# Base_board_V1.net
KiCad netlist of a schematic drawn in EAGLE
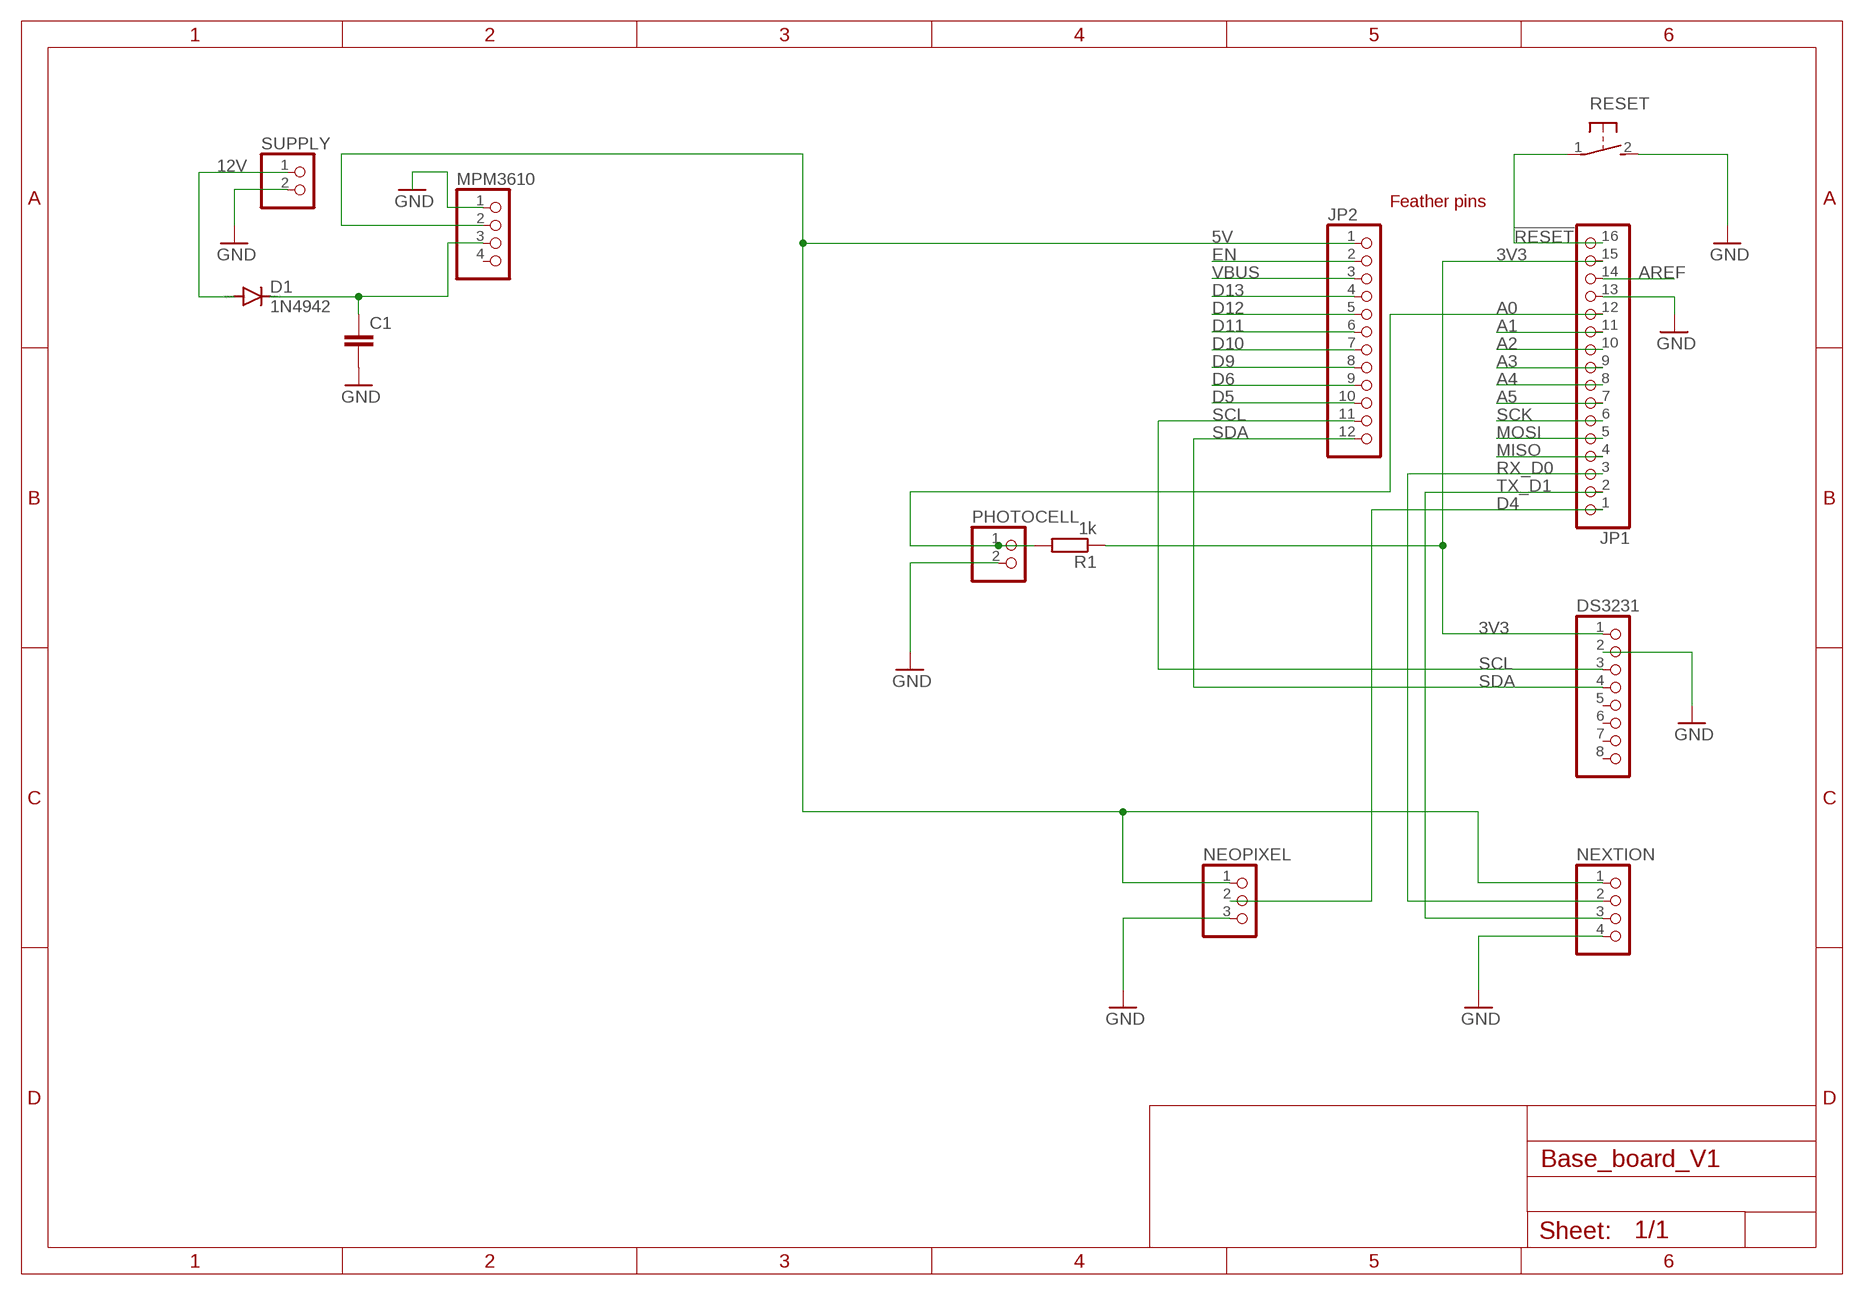
[diagram p0: schematic, sheet 1]

(export (version "E")
  (design (tool "Eeschema 10.0.6"))
  (components
    (comp (ref "C1")
      (value "C2,5-3")
      (footprint "eagle-import:C2.5-3")
      (libsource (lib "eagle-import") (part "C2,5-3"))
    )
    (comp (ref "D1")
      (value "1N4942")
      (footprint "eagle-import:DO41-10")
      (libsource (lib "eagle-import") (part "1N4942"))
    )
    (comp (ref "DS3231")
      (value "HEADER-1X870MIL")
      (footprint "eagle-import:1X08_ROUND_70")
      (libsource (lib "eagle-import") (part "HEADER-1X870MIL"))
    )
    (comp (ref "JP1")
      (value "HEADER-1X16ROUND")
      (footprint "eagle-import:1X16_ROUND")
      (libsource (lib "eagle-import") (part "HEADER-1X16ROUND"))
    )
    (comp (ref "JP2")
      (value "HEADER-1X12")
      (footprint "eagle-import:1X12_ROUND")
      (libsource (lib "eagle-import") (part "HEADER-1X12"))
    )
    (comp (ref "MPM3610")
      (value "PINHD-1X4")
      (footprint "eagle-import:1X04")
      (libsource (lib "eagle-import") (part "PINHD-1X4"))
    )
    (comp (ref "NEOPIXEL")
      (value "PINHD-1X3/90")
      (footprint "eagle-import:1X03_90")
      (libsource (lib "eagle-import") (part "PINHD-1X3/90"))
    )
    (comp (ref "NEXTION")
      (value "PINHD-1X4")
      (footprint "eagle-import:1X04")
      (libsource (lib "eagle-import") (part "PINHD-1X4"))
    )
    (comp (ref "PHOTOCELL")
      (value "PINHD-1X2/90")
      (footprint "eagle-import:1X02_90")
      (libsource (lib "eagle-import") (part "PINHD-1X2/90"))
    )
    (comp (ref "R1")
      (value "1k")
      (footprint "eagle-import:0207_10")
      (libsource (lib "eagle-import") (part "R-EU_0207/10"))
    )
    (comp (ref "RESET")
      (value "31-XX")
      (footprint "eagle-import:B3F-31XX")
      (fields (field (name "MPN") "B3F-3100"))
      (libsource (lib "eagle-import") (part "31-XX"))
    )
    (comp (ref "SUPPLY")
      (value "PINHD-1X2")
      (footprint "eagle-import:1X02")
      (libsource (lib "eagle-import") (part "PINHD-1X2"))
    )
  )
  (nets
    (net (code "1") (name "/3V3") (class "Default")
      (node (ref "DS3231") (pin "1") (pinfunction "1_1") (pintype "passive"))
      (node (ref "JP1") (pin "15") (pinfunction "15_15") (pintype "passive"))
      (node (ref "R1") (pin "1") (pinfunction "1_1") (pintype "passive"))
    )
    (net (code "2") (name "/5V") (class "Default")
      (node (ref "JP2") (pin "1") (pinfunction "1_1") (pintype "passive"))
      (node (ref "MPM3610") (pin "2") (pinfunction "2_2") (pintype "passive"))
      (node (ref "NEOPIXEL") (pin "1") (pinfunction "1_1") (pintype "passive"))
      (node (ref "NEXTION") (pin "1") (pinfunction "1_1") (pintype "passive"))
    )
    (net (code "3") (name "/12V") (class "Default")
      (node (ref "D1") (pin "A") (pinfunction "A_A") (pintype "passive"))
      (node (ref "SUPPLY") (pin "1") (pinfunction "1_1") (pintype "passive"))
    )
    (net (code "4") (name "/A0") (class "Default")
      (node (ref "JP1") (pin "12") (pinfunction "12_12") (pintype "passive"))
      (node (ref "PHOTOCELL") (pin "1") (pinfunction "1_1") (pintype "passive"))
      (node (ref "R1") (pin "2") (pinfunction "2_2") (pintype "passive"))
    )
    (net (code "5") (name "/A1") (class "Default")
      (node (ref "JP1") (pin "11") (pinfunction "11_11") (pintype "passive"))
    )
    (net (code "6") (name "/A2") (class "Default")
      (node (ref "JP1") (pin "10") (pinfunction "10_10") (pintype "passive"))
    )
    (net (code "7") (name "/A3") (class "Default")
      (node (ref "JP1") (pin "9") (pinfunction "9_9") (pintype "passive"))
    )
    (net (code "8") (name "/A4") (class "Default")
      (node (ref "JP1") (pin "8") (pinfunction "8_8") (pintype "passive"))
    )
    (net (code "9") (name "/A5") (class "Default")
      (node (ref "JP1") (pin "7") (pinfunction "7_7") (pintype "passive"))
    )
    (net (code "10") (name "/AREF") (class "Default")
      (node (ref "JP1") (pin "14") (pinfunction "14_14") (pintype "passive"))
    )
    (net (code "11") (name "/D4") (class "Default")
      (node (ref "JP1") (pin "1") (pinfunction "1_1") (pintype "passive"))
      (node (ref "NEOPIXEL") (pin "2") (pinfunction "2_2") (pintype "passive"))
    )
    (net (code "12") (name "/D5") (class "Default")
      (node (ref "JP2") (pin "10") (pinfunction "10_10") (pintype "passive"))
    )
    (net (code "13") (name "/D6") (class "Default")
      (node (ref "JP2") (pin "9") (pinfunction "9_9") (pintype "passive"))
    )
    (net (code "14") (name "/D9") (class "Default")
      (node (ref "JP2") (pin "8") (pinfunction "8_8") (pintype "passive"))
    )
    (net (code "15") (name "/D10") (class "Default")
      (node (ref "JP2") (pin "7") (pinfunction "7_7") (pintype "passive"))
    )
    (net (code "16") (name "/D11") (class "Default")
      (node (ref "JP2") (pin "6") (pinfunction "6_6") (pintype "passive"))
    )
    (net (code "17") (name "/D12") (class "Default")
      (node (ref "JP2") (pin "5") (pinfunction "5_5") (pintype "passive"))
    )
    (net (code "18") (name "/D13") (class "Default")
      (node (ref "JP2") (pin "4") (pinfunction "4_4") (pintype "passive"))
    )
    (net (code "19") (name "/EN") (class "Default")
      (node (ref "JP2") (pin "2") (pinfunction "2_2") (pintype "passive"))
    )
    (net (code "20") (name "/MISO") (class "Default")
      (node (ref "JP1") (pin "4") (pinfunction "4_4") (pintype "passive"))
    )
    (net (code "21") (name "/MOSI") (class "Default")
      (node (ref "JP1") (pin "5") (pinfunction "5_5") (pintype "passive"))
    )
    (net (code "22") (name "/RX_D0") (class "Default")
      (node (ref "JP1") (pin "3") (pinfunction "3_3") (pintype "passive"))
      (node (ref "NEXTION") (pin "2") (pinfunction "2_2") (pintype "passive"))
    )
    (net (code "23") (name "/SCK") (class "Default")
      (node (ref "JP1") (pin "6") (pinfunction "6_6") (pintype "passive"))
    )
    (net (code "24") (name "/SCL") (class "Default")
      (node (ref "DS3231") (pin "3") (pinfunction "3_3") (pintype "passive"))
      (node (ref "JP2") (pin "11") (pinfunction "11_11") (pintype "passive"))
    )
    (net (code "25") (name "/SDA") (class "Default")
      (node (ref "DS3231") (pin "4") (pinfunction "4_4") (pintype "passive"))
      (node (ref "JP2") (pin "12") (pinfunction "12_12") (pintype "passive"))
    )
    (net (code "26") (name "/TX_D1") (class "Default")
      (node (ref "JP1") (pin "2") (pinfunction "2_2") (pintype "passive"))
      (node (ref "NEXTION") (pin "3") (pinfunction "3_3") (pintype "passive"))
    )
    (net (code "27") (name "/VBUS") (class "Default")
      (node (ref "JP2") (pin "3") (pinfunction "3_3") (pintype "passive"))
    )
    (net (code "28") (name "/~{RESET}") (class "Default")
      (node (ref "JP1") (pin "16") (pinfunction "16_16") (pintype "passive"))
      (node (ref "RESET") (pin "1") (pinfunction "P_1") (pintype "passive"))
    )
    (net (code "29") (name "GND") (class "Default")
      (node (ref "C1") (pin "2") (pinfunction "2_2") (pintype "passive"))
      (node (ref "DS3231") (pin "2") (pinfunction "2_2") (pintype "passive"))
      (node (ref "JP1") (pin "13") (pinfunction "13_13") (pintype "passive"))
      (node (ref "MPM3610") (pin "1") (pinfunction "1_1") (pintype "passive"))
      (node (ref "NEOPIXEL") (pin "3") (pinfunction "3_3") (pintype "passive"))
      (node (ref "NEXTION") (pin "4") (pinfunction "4_4") (pintype "passive"))
      (node (ref "PHOTOCELL") (pin "2") (pinfunction "2_2") (pintype "passive"))
      (node (ref "RESET") (pin "2") (pinfunction "S_2") (pintype "passive"))
      (node (ref "SUPPLY") (pin "2") (pinfunction "2_2") (pintype "passive"))
    )
    (net (code "30") (name "Net-(C1-Pad1)") (class "Default")
      (node (ref "C1") (pin "1") (pinfunction "1_1") (pintype "passive"))
      (node (ref "D1") (pin "C") (pinfunction "C_C") (pintype "passive"))
      (node (ref "MPM3610") (pin "3") (pinfunction "3_3") (pintype "passive"))
    )
    (net (code "31") (name "unconnected-(DS3231-Pad5)") (class "Default")
      (node (ref "DS3231") (pin "5") (pinfunction "5_5") (pintype "passive"))
    )
    (net (code "32") (name "unconnected-(DS3231-Pad6)") (class "Default")
      (node (ref "DS3231") (pin "6") (pinfunction "6_6") (pintype "passive"))
    )
    (net (code "33") (name "unconnected-(DS3231-Pad7)") (class "Default")
      (node (ref "DS3231") (pin "7") (pinfunction "7_7") (pintype "passive"))
    )
    (net (code "34") (name "unconnected-(DS3231-Pad8)") (class "Default")
      (node (ref "DS3231") (pin "8") (pinfunction "8_8") (pintype "passive"))
    )
    (net (code "35") (name "unconnected-(MPM3610-Pad4)") (class "Default")
      (node (ref "MPM3610") (pin "4") (pinfunction "4_4") (pintype "passive"))
    )
  )
)
